# design.net
KiCad netlist of a schematic drawn in EasyEDA Pro
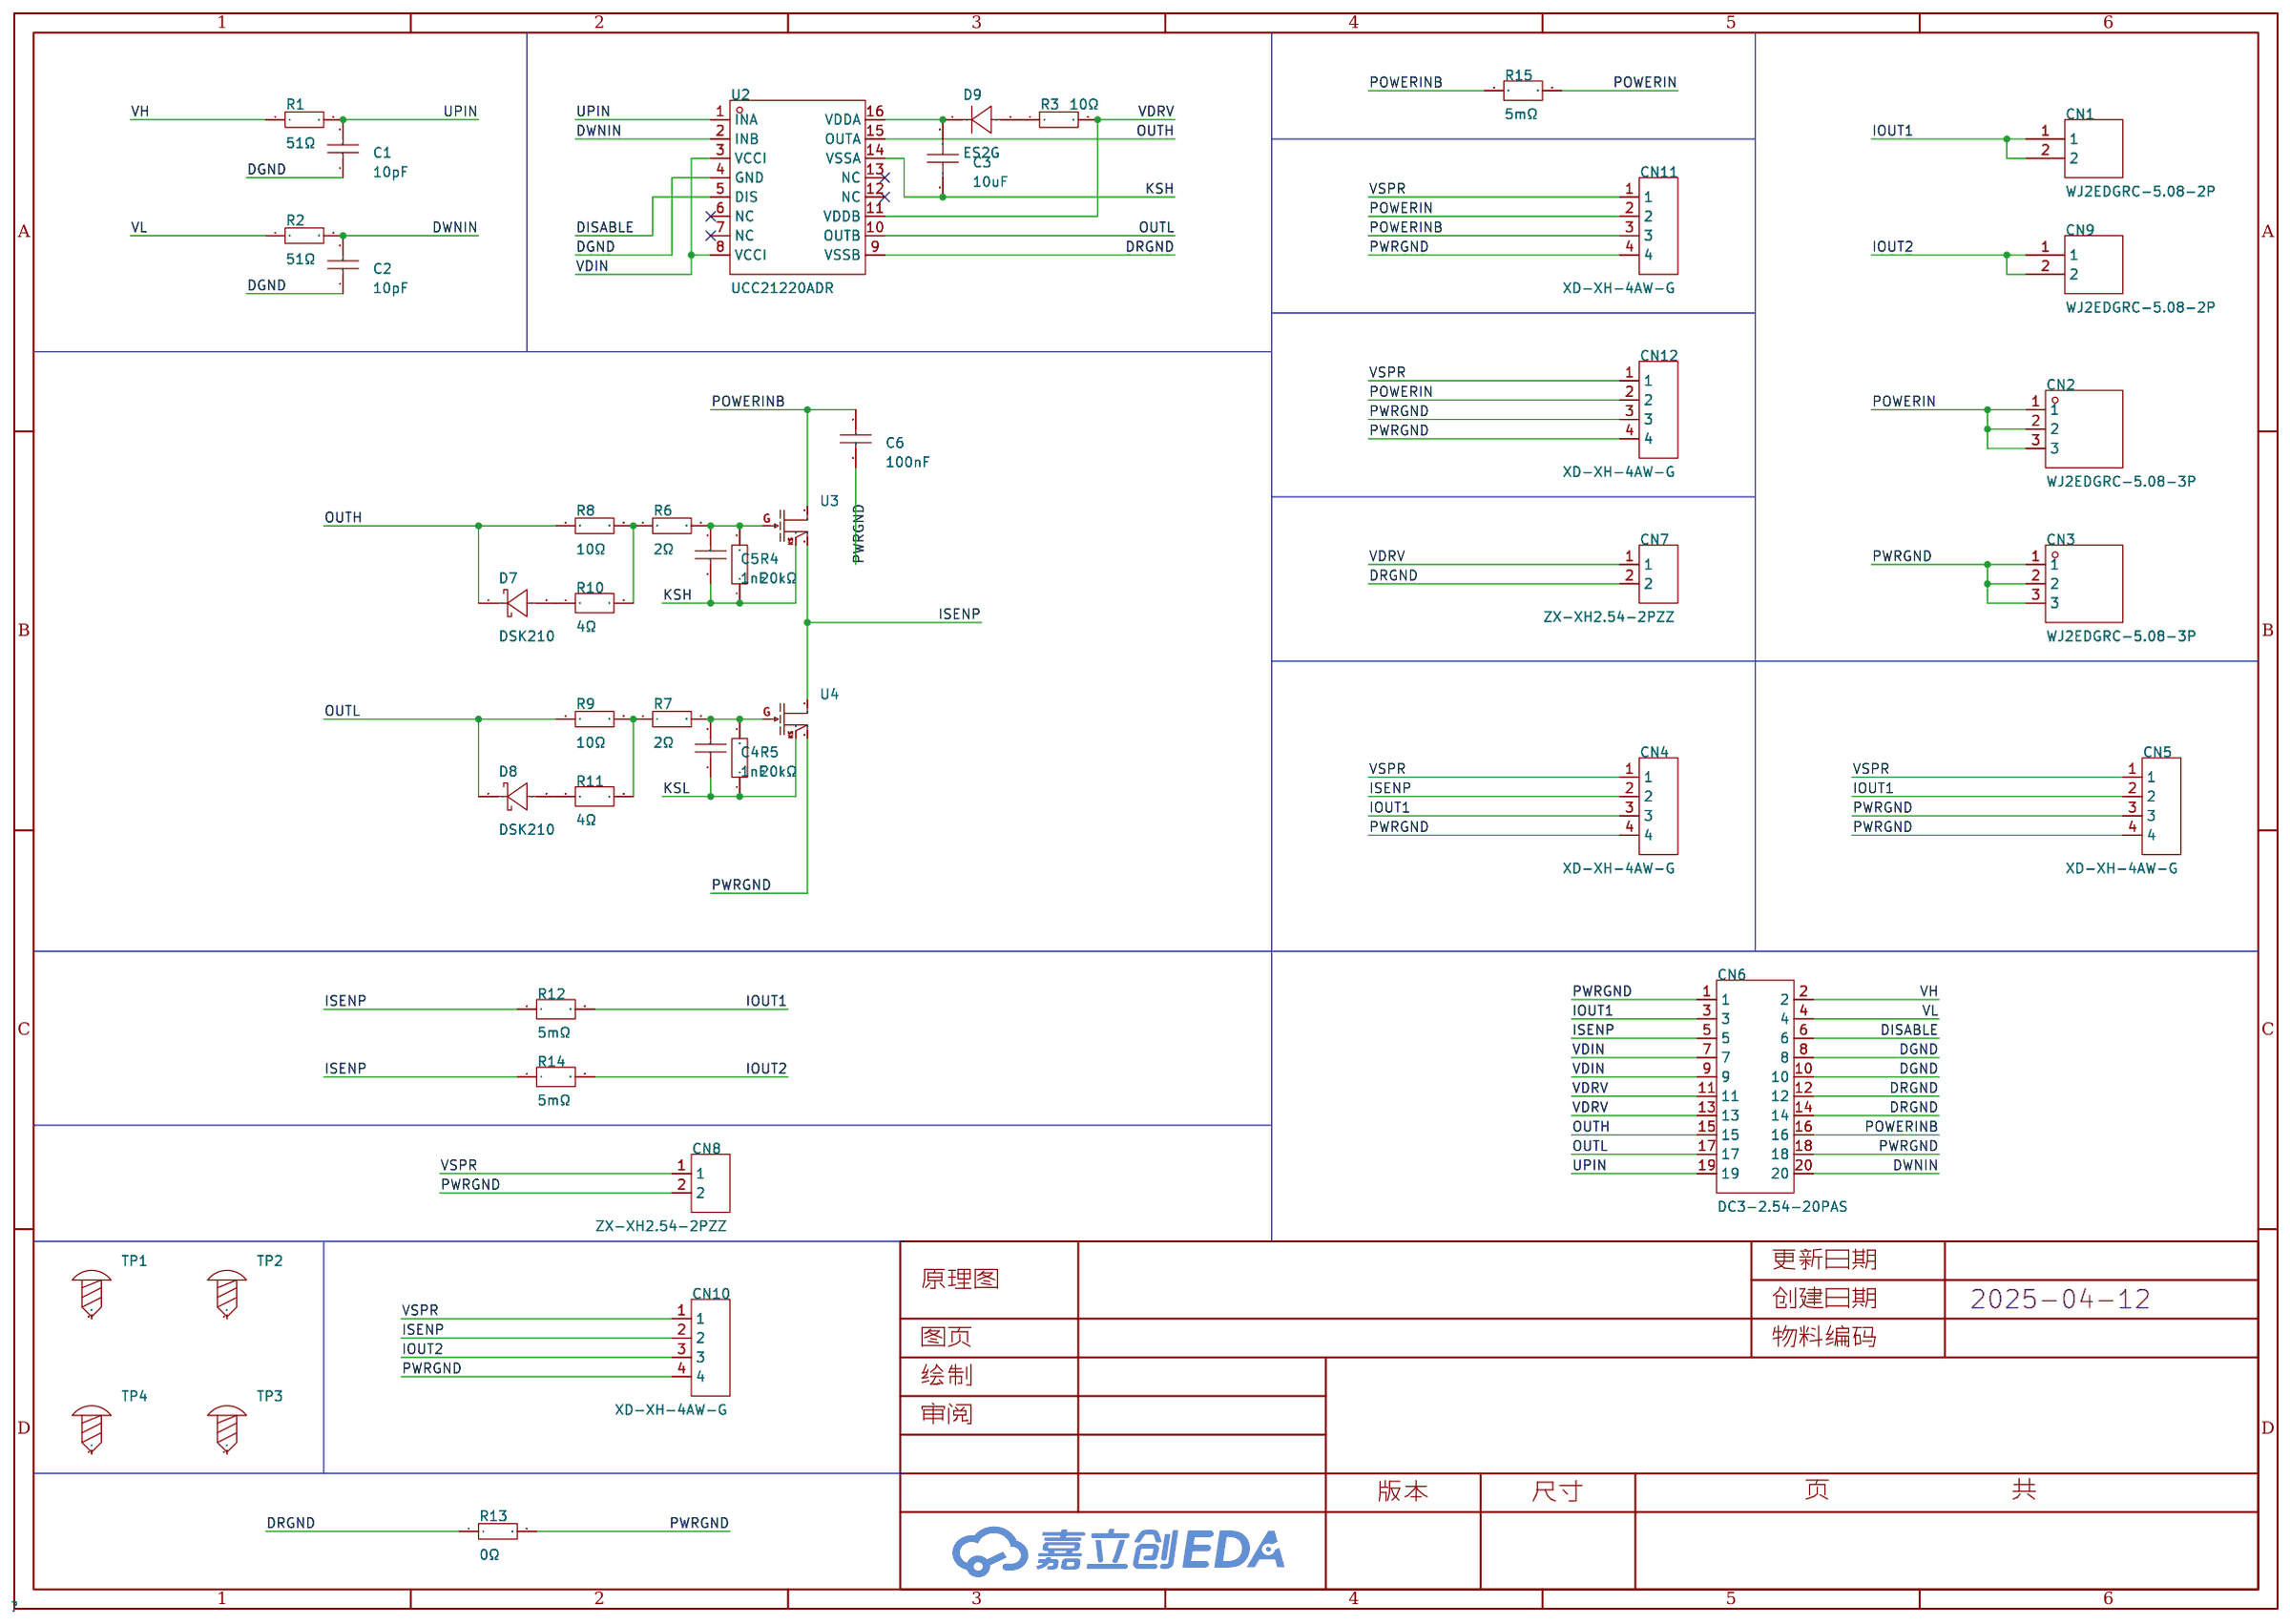
[diagram p0: schematic sheet]

(export (version "E")
  (design (tool "Eeschema 10.0.6"))
  (components
    (comp (ref "C1")
      (value "10pF")
      (footprint "easyedapro:C0603")
      (description "容值:10pF;精度:±5%;额定电压:50V;材质(温度系数):NP0;")
      (fields
        (field (name "Manufacturer Part") "CC0603JRNPO9BN100")
        (field (name "Manufacturer") "YAGEO(国巨)")
      )
      (libsource (lib "easyedapro") (part "CC0603JRNPO9BN100"))
    )
    (comp (ref "C2")
      (value "10pF")
      (footprint "easyedapro:C0603")
      (description "容值:10pF;精度:±5%;额定电压:50V;材质(温度系数):NP0;")
      (fields
        (field (name "Manufacturer Part") "CC0603JRNPO9BN100")
        (field (name "Manufacturer") "YAGEO(国巨)")
      )
      (libsource (lib "easyedapro") (part "CC0603JRNPO9BN100"))
    )
    (comp (ref "C3")
      (value "10uF")
      (footprint "easyedapro:C0805")
      (description "容值:10uF;精度:±10%;额定电压:25V;材质(温度系数):X5R;")
      (fields
        (field (name "Manufacturer Part") "CL21A106KAYNNNE")
        (field (name "Manufacturer") "SAMSUNG(三星)")
      )
      (libsource (lib "easyedapro") (part "CL21A106KAYNNNE"))
    )
    (comp (ref "C4")
      (value "1nF")
      (footprint "easyedapro:C0603")
      (description "容值:1nF;精度:±10%;额定电压:50V;材质(温度系数):X7R;")
      (fields
        (field (name "Manufacturer Part") "CL10B102KB8NNNC")
        (field (name "Manufacturer") "SAMSUNG(三星)")
      )
      (libsource (lib "easyedapro") (part "CL10B102KB8NNNC"))
    )
    (comp (ref "C5")
      (value "1nF")
      (footprint "easyedapro:C0603")
      (description "容值:1nF;精度:±10%;额定电压:50V;材质(温度系数):X7R;")
      (fields
        (field (name "Manufacturer Part") "CL10B102KB8NNNC")
        (field (name "Manufacturer") "SAMSUNG(三星)")
      )
      (libsource (lib "easyedapro") (part "CL10B102KB8NNNC"))
    )
    (comp (ref "C6")
      (value "100nF")
      (footprint "easyedapro:C1210")
      (description "容值:100nF;精度:±20%;额定电压:350V;温度系数:X7R;")
      (fields (field (name "Manufacturer Part") "C1210X104M351T") (field (name "Manufacturer") "IHHEC(禾伸堂)"))
      (libsource (lib "easyedapro") (part "C1210X104M351T"))
    )
    (comp (ref "CN1")
      (value "WJ2EDGRC-5.08-2P")
      (footprint "easyedapro:CONN-TH_2P-P5.08_WJ2EDGRC-5.08-2P")
      (fields (field (name "Manufacturer") "KANGNEX(康奈克斯电气)"))
      (libsource (lib "easyedapro") (part "WJ2EDGRC-5.08-2P"))
    )
    (comp (ref "CN2")
      (value "WJ2EDGRC-5.08-3P")
      (footprint "easyedapro:CONN-TH_3P-P5.08_WJ2EDGRC-5.08-3P")
      (fields (field (name "Manufacturer") "KANGNEX(康奈克斯电气)"))
      (libsource (lib "easyedapro") (part "WJ2EDGRC-5.08-3P_C8377"))
    )
    (comp (ref "CN3")
      (value "WJ2EDGRC-5.08-3P")
      (footprint "easyedapro:CONN-TH_3P-P5.08_WJ2EDGRC-5.08-3P")
      (fields (field (name "Manufacturer") "KANGNEX(康奈克斯电气)"))
      (libsource (lib "easyedapro") (part "WJ2EDGRC-5.08-3P_C8377"))
    )
    (comp (ref "CN4")
      (value "XD-XH-4AW-G")
      (footprint "easyedapro:CONN-TH_XD-XH-4AW-G")
      (description "插针结构:1x4P;间距:2.54mm;安装方式:弯插;参考系列:XH;总PIN数:4P;排数:1;每排PIN数:4;行距:2.54mm;额定电流:3A;工作温度:-25°C~+85°C;")
      (fields (field (name "Manufacturer") "XUNDA(讯答)"))
      (libsource (lib "easyedapro") (part "XD-XH-4AW-G"))
    )
    (comp (ref "CN5")
      (value "XD-XH-4AW-G")
      (footprint "easyedapro:CONN-TH_XD-XH-4AW-G")
      (description "插针结构:1x4P;间距:2.54mm;安装方式:弯插;参考系列:XH;总PIN数:4P;排数:1;每排PIN数:4;行距:2.54mm;额定电流:3A;工作温度:-25°C~+85°C;")
      (fields (field (name "Manufacturer") "XUNDA(讯答)"))
      (libsource (lib "easyedapro") (part "XD-XH-4AW-G"))
    )
    (comp (ref "CN6")
      (value "DC3-2.54-20PAS")
      (footprint "easyedapro:HDR-TH_20P-P2.54_DC3-2.54-20PAS")
      (fields (field (name "Manufacturer") "ZHOURI(洲日)"))
      (libsource (lib "easyedapro") (part "DC3-2.54-20PAS"))
    )
    (comp (ref "CN7")
      (value "ZX-XH2.54-2PZZ")
      (footprint "easyedapro:CONN-TH_2P-P2.50_HX25003-2A")
      (fields (field (name "Manufacturer") "Megastar(兆星)"))
      (libsource (lib "easyedapro") (part "ZX-XH2.54-2PZZ"))
    )
    (comp (ref "CN8")
      (value "ZX-XH2.54-2PZZ")
      (footprint "easyedapro:CONN-TH_2P-P2.50_HX25003-2A")
      (fields (field (name "Manufacturer") "Megastar(兆星)"))
      (libsource (lib "easyedapro") (part "ZX-XH2.54-2PZZ"))
    )
    (comp (ref "CN9")
      (value "WJ2EDGRC-5.08-2P")
      (footprint "easyedapro:CONN-TH_2P-P5.08_WJ2EDGRC-5.08-2P")
      (fields (field (name "Manufacturer") "KANGNEX(康奈克斯电气)"))
      (libsource (lib "easyedapro") (part "WJ2EDGRC-5.08-2P"))
    )
    (comp (ref "CN10")
      (value "XD-XH-4AW-G")
      (footprint "easyedapro:CONN-TH_XD-XH-4AW-G")
      (description "插针结构:1x4P;间距:2.54mm;安装方式:弯插;参考系列:XH;总PIN数:4P;排数:1;每排PIN数:4;行距:2.54mm;额定电流:3A;工作温度:-25°C~+85°C;")
      (fields (field (name "Manufacturer") "XUNDA(讯答)"))
      (libsource (lib "easyedapro") (part "XD-XH-4AW-G"))
    )
    (comp (ref "CN11")
      (value "XD-XH-4AW-G")
      (footprint "easyedapro:CONN-TH_XD-XH-4AW-G")
      (description "插针结构:1x4P;间距:2.54mm;安装方式:弯插;参考系列:XH;总PIN数:4P;排数:1;每排PIN数:4;行距:2.54mm;额定电流:3A;工作温度:-25°C~+85°C;")
      (fields (field (name "Manufacturer") "XUNDA(讯答)"))
      (libsource (lib "easyedapro") (part "XD-XH-4AW-G"))
    )
    (comp (ref "CN12")
      (value "XD-XH-4AW-G")
      (footprint "easyedapro:CONN-TH_XD-XH-4AW-G")
      (description "插针结构:1x4P;间距:2.54mm;安装方式:弯插;参考系列:XH;总PIN数:4P;排数:1;每排PIN数:4;行距:2.54mm;额定电流:3A;工作温度:-25°C~+85°C;")
      (fields (field (name "Manufacturer") "XUNDA(讯答)"))
      (libsource (lib "easyedapro") (part "XD-XH-4AW-G"))
    )
    (comp (ref "D7")
      (value "DSK210")
      (footprint "easyedapro:SOD-123FL_L2.7-W1.8-LS3.8-RD")
      (description "二极管配置:独立式;正向压降(Vf):850mV@2A;直流反向耐压(Vr):100V;整流电流:2A;")
      (fields (field (name "Manufacturer") "宏迦橙"))
      (libsource (lib "easyedapro") (part "DSK210_C7502713"))
    )
    (comp (ref "D8")
      (value "DSK210")
      (footprint "easyedapro:SOD-123FL_L2.7-W1.8-LS3.8-RD")
      (description "二极管配置:独立式;正向压降(Vf):850mV@2A;直流反向耐压(Vr):100V;整流电流:2A;")
      (fields (field (name "Manufacturer") "宏迦橙"))
      (libsource (lib "easyedapro") (part "DSK210_C7502713"))
    )
    (comp (ref "D9")
      (value "ES2G")
      (footprint "easyedapro:SMA_L4.3-W2.6-LS5.0-RD")
      (description "二极管配置:独立式;正向压降(Vf):1.3V@2A;直流反向耐压(Vr):400V;整流电流:2A;反向恢复时间(Trr):35ns;")
      (fields (field (name "Manufacturer") "宏嘉诚"))
      (libsource (lib "easyedapro") (part "ES2G_C18199140"))
    )
    (comp (ref "R1")
      (value "51Ω")
      (footprint "easyedapro:R0603")
      (description "电阻类型:厚膜电阻;阻值:51Ω;精度:±1%;功率:100mW;最大工作电压:75V;温度系数:±100ppm/°C;")
      (fields
        (field (name "Manufacturer Part") "0603WAF510JT5E")
        (field (name "Manufacturer") "UNI-ROYAL(厚声)")
      )
      (libsource (lib "easyedapro") (part "0603WAF510JT5E"))
    )
    (comp (ref "R2")
      (value "51Ω")
      (footprint "easyedapro:R0603")
      (description "电阻类型:厚膜电阻;阻值:51Ω;精度:±1%;功率:100mW;最大工作电压:75V;温度系数:±100ppm/°C;")
      (fields
        (field (name "Manufacturer Part") "0603WAF510JT5E")
        (field (name "Manufacturer") "UNI-ROYAL(厚声)")
      )
      (libsource (lib "easyedapro") (part "0603WAF510JT5E"))
    )
    (comp (ref "R3")
      (value "10Ω")
      (footprint "easyedapro:R0805_NEW")
      (description "电阻类型:厚膜电阻;阻值:10Ω;精度:±1%;功率:125mW;最大工作电压:150V;温度系数:±200ppm/°C;")
      (fields
        (field (name "Manufacturer Part") "0805W8F100JT5E")
        (field (name "Manufacturer") "UNI-ROYAL(厚声)")
      )
      (libsource (lib "easyedapro") (part "0805W8F100JT5E"))
    )
    (comp (ref "R4")
      (value "20kΩ")
      (footprint "easyedapro:R0603")
      (description "电阻类型:厚膜电阻;阻值:20kΩ;精度:±1%;功率:100mW;最大工作电压:75V;温度系数:±100ppm/°C;")
      (fields
        (field (name "Manufacturer Part") "0603WAF2002T5E")
        (field (name "Manufacturer") "UNI-ROYAL(厚声)")
      )
      (libsource (lib "easyedapro") (part "0603WAF2002T5E"))
    )
    (comp (ref "R5")
      (value "20kΩ")
      (footprint "easyedapro:R0603")
      (description "电阻类型:厚膜电阻;阻值:20kΩ;精度:±1%;功率:100mW;最大工作电压:75V;温度系数:±100ppm/°C;")
      (fields
        (field (name "Manufacturer Part") "0603WAF2002T5E")
        (field (name "Manufacturer") "UNI-ROYAL(厚声)")
      )
      (libsource (lib "easyedapro") (part "0603WAF2002T5E"))
    )
    (comp (ref "R6")
      (value "2Ω")
      (footprint "easyedapro:R0603")
      (description "电阻类型:厚膜电阻;阻值:2Ω;精度:±1%;功率:100mW;最大工作电压:75V;温度系数:±200ppm/°C;")
      (fields
        (field (name "Manufacturer Part") "0603WAF200KT5E")
        (field (name "Manufacturer") "UNI-ROYAL(厚声)")
      )
      (libsource (lib "easyedapro") (part "0603WAF200KT5E"))
    )
    (comp (ref "R7")
      (value "2Ω")
      (footprint "easyedapro:R0603")
      (description "电阻类型:厚膜电阻;阻值:2Ω;精度:±1%;功率:100mW;最大工作电压:75V;温度系数:±200ppm/°C;")
      (fields
        (field (name "Manufacturer Part") "0603WAF200KT5E")
        (field (name "Manufacturer") "UNI-ROYAL(厚声)")
      )
      (libsource (lib "easyedapro") (part "0603WAF200KT5E"))
    )
    (comp (ref "R8")
      (value "10Ω")
      (footprint "easyedapro:R0603")
      (description "电阻类型:厚膜电阻;阻值:10Ω;精度:±1%;功率:100mW;最大工作电压:75V;温度系数:±400ppm/°C;")
      (fields
        (field (name "Manufacturer Part") "0603WAF100JT5E")
        (field (name "Manufacturer") "UNI-ROYAL(厚声)")
      )
      (libsource (lib "easyedapro") (part "0603WAF100JT5E"))
    )
    (comp (ref "R9")
      (value "10Ω")
      (footprint "easyedapro:R0603")
      (description "电阻类型:厚膜电阻;阻值:10Ω;精度:±1%;功率:100mW;最大工作电压:75V;温度系数:±400ppm/°C;")
      (fields
        (field (name "Manufacturer Part") "0603WAF100JT5E")
        (field (name "Manufacturer") "UNI-ROYAL(厚声)")
      )
      (libsource (lib "easyedapro") (part "0603WAF100JT5E"))
    )
    (comp (ref "R10")
      (value "4Ω")
      (footprint "easyedapro:R0603")
      (description "电阻类型:厚膜电阻;阻值:4Ω;精度:±1%;功率:100mW;温度系数:±200ppm/°C;")
      (fields (field (name "Manufacturer Part") "CR164R00F") (field (name "Manufacturer") "Meritek"))
      (libsource (lib "easyedapro") (part "CR164R00F"))
    )
    (comp (ref "R11")
      (value "4Ω")
      (footprint "easyedapro:R0603")
      (description "电阻类型:厚膜电阻;阻值:4Ω;精度:±1%;功率:100mW;温度系数:±200ppm/°C;")
      (fields (field (name "Manufacturer Part") "CR164R00F") (field (name "Manufacturer") "Meritek"))
      (libsource (lib "easyedapro") (part "CR164R00F"))
    )
    (comp (ref "R12")
      (value "5mΩ")
      (footprint "easyedapro:RES-SMD_L6.4-W3.2-1")
      (description "电阻类型:采样电阻;阻值:5mΩ;精度:±1%;功率:3W;安装方式:贴片;")
      (fields
        (field (name "Manufacturer Part") "HoJLR2512-3W-5mR-1%")
        (field (name "Manufacturer") "Milliohm(毫欧)")
      )
      (libsource (lib "easyedapro") (part "HOJLR2512-3W-5MR-1%"))
    )
    (comp (ref "R13")
      (value "0Ω")
      (footprint "easyedapro:R0805")
      (description "电阻类型:厚膜电阻;阻值:0Ω;精度:±1%;功率:125mW;最大工作电压:150V;温度系数:±800ppm/°C;")
      (fields
        (field (name "Manufacturer Part") "0805W8F0000T5E")
        (field (name "Manufacturer") "UNI-ROYAL(厚声)")
      )
      (libsource (lib "easyedapro") (part "0805W8F0000T5E"))
    )
    (comp (ref "R14")
      (value "5mΩ")
      (footprint "easyedapro:RES-SMD_L6.4-W3.2-1")
      (description "电阻类型:采样电阻;阻值:5mΩ;精度:±1%;功率:3W;安装方式:贴片;")
      (fields
        (field (name "Manufacturer Part") "HoJLR2512-3W-5mR-1%")
        (field (name "Manufacturer") "Milliohm(毫欧)")
      )
      (libsource (lib "easyedapro") (part "HOJLR2512-3W-5MR-1%"))
    )
    (comp (ref "R15")
      (value "5mΩ")
      (footprint "easyedapro:RES-SMD_L6.4-W3.2-1")
      (description "电阻类型:采样电阻;阻值:5mΩ;精度:±1%;功率:3W;安装方式:贴片;")
      (fields
        (field (name "Manufacturer Part") "HoJLR2512-3W-5mR-1%")
        (field (name "Manufacturer") "Milliohm(毫欧)")
      )
      (libsource (lib "easyedapro") (part "HOJLR2512-3W-5MR-1%"))
    )
    (comp (ref "TP1") (value "~") (footprint "easyedapro:M3螺丝") (libsource (lib "easyedapro") (part "螺丝孔")))
    (comp (ref "TP2") (value "~") (footprint "easyedapro:M3螺丝") (libsource (lib "easyedapro") (part "螺丝孔")))
    (comp (ref "TP3") (value "~") (footprint "easyedapro:M3螺丝") (libsource (lib "easyedapro") (part "螺丝孔")))
    (comp (ref "TP4") (value "~") (footprint "easyedapro:M3螺丝") (libsource (lib "easyedapro") (part "螺丝孔")))
    (comp (ref "U2")
      (value "UCC21220ADR")
      (footprint "easyedapro:SOIC-16_L9.9-W3.9-P1.27-LS6.0-BL")
      (fields (field (name "Manufacturer") "TI(德州仪器)"))
      (libsource (lib "easyedapro") (part "UCC21220ADR"))
    )
    (comp (ref "U3")
      (value "~")
      (footprint "easyedapro:INN650TA030AH")
      (libsource (lib "easyedapro") (part "INN650TA030AH"))
    )
    (comp (ref "U4")
      (value "~")
      (footprint "easyedapro:INN650TA030AH")
      (libsource (lib "easyedapro") (part "INN650TA030AH"))
    )
  )
  (nets
    (net (code "1") (name "/DGND") (class "Default")
      (node (ref "C1") (pin "1") (pinfunction "1_1") (pintype "input"))
      (node (ref "C2") (pin "1") (pinfunction "1_1") (pintype "input"))
      (node (ref "CN6") (pin "10") (pinfunction "10_10") (pintype "unspecified"))
      (node (ref "CN6") (pin "8") (pinfunction "8_8") (pintype "unspecified"))
      (node (ref "U2") (pin "4") (pinfunction "GND_4") (pintype "unspecified"))
    )
    (net (code "2") (name "/DISABLE") (class "Default")
      (node (ref "CN6") (pin "6") (pinfunction "6_6") (pintype "unspecified"))
      (node (ref "U2") (pin "5") (pinfunction "DIS_5") (pintype "unspecified"))
    )
    (net (code "3") (name "/DRGND") (class "Default")
      (node (ref "CN6") (pin "12") (pinfunction "12_12") (pintype "unspecified"))
      (node (ref "CN6") (pin "14") (pinfunction "14_14") (pintype "unspecified"))
      (node (ref "CN7") (pin "2") (pinfunction "2_2") (pintype "unspecified"))
      (node (ref "R13") (pin "1") (pinfunction "1_1") (pintype "input"))
      (node (ref "U2") (pin "9") (pinfunction "VSSB_9") (pintype "unspecified"))
    )
    (net (code "4") (name "/DWNIN") (class "Default")
      (node (ref "C2") (pin "2") (pinfunction "2_2") (pintype "input"))
      (node (ref "CN6") (pin "20") (pinfunction "20_20") (pintype "unspecified"))
      (node (ref "R2") (pin "2") (pinfunction "2_2") (pintype "input"))
      (node (ref "U2") (pin "2") (pinfunction "INB_2") (pintype "unspecified"))
    )
    (net (code "5") (name "/IOUT1") (class "Default")
      (node (ref "CN1") (pin "1") (pinfunction "1_1") (pintype "unspecified"))
      (node (ref "CN1") (pin "2") (pinfunction "2_2") (pintype "unspecified"))
      (node (ref "CN4") (pin "3") (pinfunction "3_3") (pintype "unspecified"))
      (node (ref "CN5") (pin "2") (pinfunction "2_2") (pintype "unspecified"))
      (node (ref "CN6") (pin "3") (pinfunction "3_3") (pintype "unspecified"))
      (node (ref "R12") (pin "2") (pinfunction "2_2") (pintype "unspecified"))
    )
    (net (code "6") (name "/IOUT2") (class "Default")
      (node (ref "CN10") (pin "3") (pinfunction "3_3") (pintype "unspecified"))
      (node (ref "CN9") (pin "1") (pinfunction "1_1") (pintype "unspecified"))
      (node (ref "CN9") (pin "2") (pinfunction "2_2") (pintype "unspecified"))
      (node (ref "R14") (pin "2") (pinfunction "2_2") (pintype "unspecified"))
    )
    (net (code "7") (name "/ISENP") (class "Default")
      (node (ref "CN10") (pin "2") (pinfunction "2_2") (pintype "unspecified"))
      (node (ref "CN4") (pin "2") (pinfunction "2_2") (pintype "unspecified"))
      (node (ref "CN6") (pin "5") (pinfunction "5_5") (pintype "unspecified"))
      (node (ref "R12") (pin "1") (pinfunction "1_1") (pintype "unspecified"))
      (node (ref "R14") (pin "1") (pinfunction "1_1") (pintype "unspecified"))
      (node (ref "U3") (pin "S") (pinfunction "2_S") (pintype "input"))
      (node (ref "U4") (pin "D") (pinfunction "1_D") (pintype "input"))
    )
    (net (code "8") (name "/KSH") (class "Default")
      (node (ref "C3") (pin "1") (pinfunction "1_1") (pintype "unspecified"))
      (node (ref "C5") (pin "1") (pinfunction "1_1") (pintype "input"))
      (node (ref "R4") (pin "1") (pinfunction "1_1") (pintype "input"))
      (node (ref "U2") (pin "14") (pinfunction "VSSA_14") (pintype "unspecified"))
      (node (ref "U3") (pin "KS") (pinfunction "2_KS") (pintype "input"))
    )
    (net (code "9") (name "/KSL") (class "Default")
      (node (ref "C4") (pin "1") (pinfunction "1_1") (pintype "input"))
      (node (ref "R5") (pin "1") (pinfunction "1_1") (pintype "input"))
      (node (ref "U4") (pin "KS") (pinfunction "2_KS") (pintype "input"))
    )
    (net (code "10") (name "/OUTH") (class "Default")
      (node (ref "CN6") (pin "15") (pinfunction "15_15") (pintype "unspecified"))
      (node (ref "D7") (pin "1") (pinfunction "K_1") (pintype "unspecified"))
      (node (ref "R8") (pin "1") (pinfunction "1_1") (pintype "input"))
      (node (ref "U2") (pin "15") (pinfunction "OUTA_15") (pintype "unspecified"))
    )
    (net (code "11") (name "/OUTL") (class "Default")
      (node (ref "CN6") (pin "17") (pinfunction "17_17") (pintype "unspecified"))
      (node (ref "D8") (pin "1") (pinfunction "K_1") (pintype "unspecified"))
      (node (ref "R9") (pin "1") (pinfunction "1_1") (pintype "input"))
      (node (ref "U2") (pin "10") (pinfunction "OUTB_10") (pintype "unspecified"))
    )
    (net (code "12") (name "/POWERIN") (class "Default")
      (node (ref "CN11") (pin "2") (pinfunction "2_2") (pintype "unspecified"))
      (node (ref "CN12") (pin "2") (pinfunction "2_2") (pintype "unspecified"))
      (node (ref "CN2") (pin "1") (pinfunction "1_1") (pintype "unspecified"))
      (node (ref "CN2") (pin "2") (pinfunction "2_2") (pintype "unspecified"))
      (node (ref "CN2") (pin "3") (pinfunction "3_3") (pintype "unspecified"))
      (node (ref "R15") (pin "2") (pinfunction "2_2") (pintype "unspecified"))
    )
    (net (code "13") (name "/POWERINB") (class "Default")
      (node (ref "C6") (pin "2") (pinfunction "2_2") (pintype "input"))
      (node (ref "CN11") (pin "3") (pinfunction "3_3") (pintype "unspecified"))
      (node (ref "CN6") (pin "16") (pinfunction "16_16") (pintype "unspecified"))
      (node (ref "R15") (pin "1") (pinfunction "1_1") (pintype "unspecified"))
      (node (ref "U3") (pin "D") (pinfunction "1_D") (pintype "input"))
    )
    (net (code "14") (name "/PWRGND") (class "Default")
      (node (ref "C6") (pin "1") (pinfunction "1_1") (pintype "input"))
      (node (ref "CN10") (pin "4") (pinfunction "4_4") (pintype "unspecified"))
      (node (ref "CN11") (pin "4") (pinfunction "4_4") (pintype "unspecified"))
      (node (ref "CN12") (pin "3") (pinfunction "3_3") (pintype "unspecified"))
      (node (ref "CN12") (pin "4") (pinfunction "4_4") (pintype "unspecified"))
      (node (ref "CN3") (pin "1") (pinfunction "1_1") (pintype "unspecified"))
      (node (ref "CN3") (pin "2") (pinfunction "2_2") (pintype "unspecified"))
      (node (ref "CN3") (pin "3") (pinfunction "3_3") (pintype "unspecified"))
      (node (ref "CN4") (pin "4") (pinfunction "4_4") (pintype "unspecified"))
      (node (ref "CN5") (pin "3") (pinfunction "3_3") (pintype "unspecified"))
      (node (ref "CN5") (pin "4") (pinfunction "4_4") (pintype "unspecified"))
      (node (ref "CN6") (pin "1") (pinfunction "1_1") (pintype "unspecified"))
      (node (ref "CN6") (pin "18") (pinfunction "18_18") (pintype "unspecified"))
      (node (ref "CN8") (pin "2") (pinfunction "2_2") (pintype "unspecified"))
      (node (ref "R13") (pin "2") (pinfunction "2_2") (pintype "input"))
      (node (ref "U4") (pin "S") (pinfunction "2_S") (pintype "input"))
    )
    (net (code "15") (name "/UPIN") (class "Default")
      (node (ref "C1") (pin "2") (pinfunction "2_2") (pintype "input"))
      (node (ref "CN6") (pin "19") (pinfunction "19_19") (pintype "unspecified"))
      (node (ref "R1") (pin "2") (pinfunction "2_2") (pintype "input"))
      (node (ref "U2") (pin "1") (pinfunction "INA_1") (pintype "unspecified"))
    )
    (net (code "16") (name "/VDIN") (class "Default")
      (node (ref "CN6") (pin "7") (pinfunction "7_7") (pintype "unspecified"))
      (node (ref "CN6") (pin "9") (pinfunction "9_9") (pintype "unspecified"))
      (node (ref "U2") (pin "3") (pinfunction "VCCI_3") (pintype "unspecified"))
      (node (ref "U2") (pin "8") (pinfunction "VCCI_8") (pintype "unspecified"))
    )
    (net (code "17") (name "/VDRV") (class "Default")
      (node (ref "CN6") (pin "11") (pinfunction "11_11") (pintype "unspecified"))
      (node (ref "CN6") (pin "13") (pinfunction "13_13") (pintype "unspecified"))
      (node (ref "CN7") (pin "1") (pinfunction "1_1") (pintype "unspecified"))
      (node (ref "R3") (pin "2") (pinfunction "2_2") (pintype "input"))
      (node (ref "U2") (pin "11") (pinfunction "VDDB_11") (pintype "unspecified"))
    )
    (net (code "18") (name "/VH") (class "Default")
      (node (ref "CN6") (pin "2") (pinfunction "2_2") (pintype "unspecified"))
      (node (ref "R1") (pin "1") (pinfunction "1_1") (pintype "input"))
    )
    (net (code "19") (name "/VL") (class "Default")
      (node (ref "CN6") (pin "4") (pinfunction "4_4") (pintype "unspecified"))
      (node (ref "R2") (pin "1") (pinfunction "1_1") (pintype "input"))
    )
    (net (code "20") (name "/VSPR") (class "Default")
      (node (ref "CN10") (pin "1") (pinfunction "1_1") (pintype "unspecified"))
      (node (ref "CN11") (pin "1") (pinfunction "1_1") (pintype "unspecified"))
      (node (ref "CN12") (pin "1") (pinfunction "1_1") (pintype "unspecified"))
      (node (ref "CN4") (pin "1") (pinfunction "1_1") (pintype "unspecified"))
      (node (ref "CN5") (pin "1") (pinfunction "1_1") (pintype "unspecified"))
      (node (ref "CN8") (pin "1") (pinfunction "1_1") (pintype "unspecified"))
    )
    (net (code "21") (name "Net-(C4-Pad2)") (class "Default")
      (node (ref "C4") (pin "2") (pinfunction "2_2") (pintype "input"))
      (node (ref "R5") (pin "2") (pinfunction "2_2") (pintype "input"))
      (node (ref "R7") (pin "2") (pinfunction "2_2") (pintype "input"))
      (node (ref "U4") (pin "G") (pinfunction "2_G") (pintype "input"))
    )
    (net (code "22") (name "Net-(C5-Pad2)") (class "Default")
      (node (ref "C5") (pin "2") (pinfunction "2_2") (pintype "input"))
      (node (ref "R4") (pin "2") (pinfunction "2_2") (pintype "input"))
      (node (ref "R6") (pin "2") (pinfunction "2_2") (pintype "input"))
      (node (ref "U3") (pin "G") (pinfunction "2_G") (pintype "input"))
    )
    (net (code "23") (name "Net-(D7-A)") (class "Default")
      (node (ref "D7") (pin "2") (pinfunction "A_2") (pintype "unspecified"))
      (node (ref "R10") (pin "1") (pinfunction "1_1") (pintype "unspecified"))
    )
    (net (code "24") (name "Net-(D8-A)") (class "Default")
      (node (ref "D8") (pin "2") (pinfunction "A_2") (pintype "unspecified"))
      (node (ref "R11") (pin "1") (pinfunction "1_1") (pintype "unspecified"))
    )
    (net (code "25") (name "Net-(D9-A)") (class "Default")
      (node (ref "D9") (pin "2") (pinfunction "A_2") (pintype "unspecified"))
      (node (ref "R3") (pin "1") (pinfunction "1_1") (pintype "input"))
    )
    (net (code "26") (name "Net-(D9-K)") (class "Default")
      (node (ref "C3") (pin "2") (pinfunction "2_2") (pintype "unspecified"))
      (node (ref "D9") (pin "1") (pinfunction "K_1") (pintype "unspecified"))
      (node (ref "U2") (pin "16") (pinfunction "VDDA_16") (pintype "unspecified"))
    )
    (net (code "27") (name "Net-(R10-Pad2)") (class "Default")
      (node (ref "R10") (pin "2") (pinfunction "2_2") (pintype "unspecified"))
      (node (ref "R6") (pin "1") (pinfunction "1_1") (pintype "input"))
      (node (ref "R8") (pin "2") (pinfunction "2_2") (pintype "input"))
    )
    (net (code "28") (name "Net-(R11-Pad2)") (class "Default")
      (node (ref "R11") (pin "2") (pinfunction "2_2") (pintype "unspecified"))
      (node (ref "R7") (pin "1") (pinfunction "1_1") (pintype "input"))
      (node (ref "R9") (pin "2") (pinfunction "2_2") (pintype "input"))
    )
    (net (code "29") (name "unconnected-(TP1-Pad1)") (class "Default")
      (node (ref "TP1") (pin "1") (pinfunction "1_1") (pintype "input"))
    )
    (net (code "30") (name "unconnected-(TP2-Pad1)") (class "Default")
      (node (ref "TP2") (pin "1") (pinfunction "1_1") (pintype "input"))
    )
    (net (code "31") (name "unconnected-(TP3-Pad1)") (class "Default")
      (node (ref "TP3") (pin "1") (pinfunction "1_1") (pintype "input"))
    )
    (net (code "32") (name "unconnected-(TP4-Pad1)") (class "Default")
      (node (ref "TP4") (pin "1") (pinfunction "1_1") (pintype "input"))
    )
    (net (code "33") (name "unconnected-(U2-NC-Pad6)") (class "Default")
      (node (ref "U2") (pin "6") (pinfunction "NC_6") (pintype "unspecified+no_connect"))
    )
    (net (code "34") (name "unconnected-(U2-NC-Pad7)") (class "Default")
      (node (ref "U2") (pin "7") (pinfunction "NC_7") (pintype "unspecified+no_connect"))
    )
    (net (code "35") (name "unconnected-(U2-NC-Pad12)") (class "Default")
      (node (ref "U2") (pin "12") (pinfunction "NC_12") (pintype "unspecified+no_connect"))
    )
    (net (code "36") (name "unconnected-(U2-NC-Pad13)") (class "Default")
      (node (ref "U2") (pin "13") (pinfunction "NC_13") (pintype "unspecified+no_connect"))
    )
  )
)
